# BreakoutPcb.net
KiCad netlist of a schematic drawn in Altium Designer
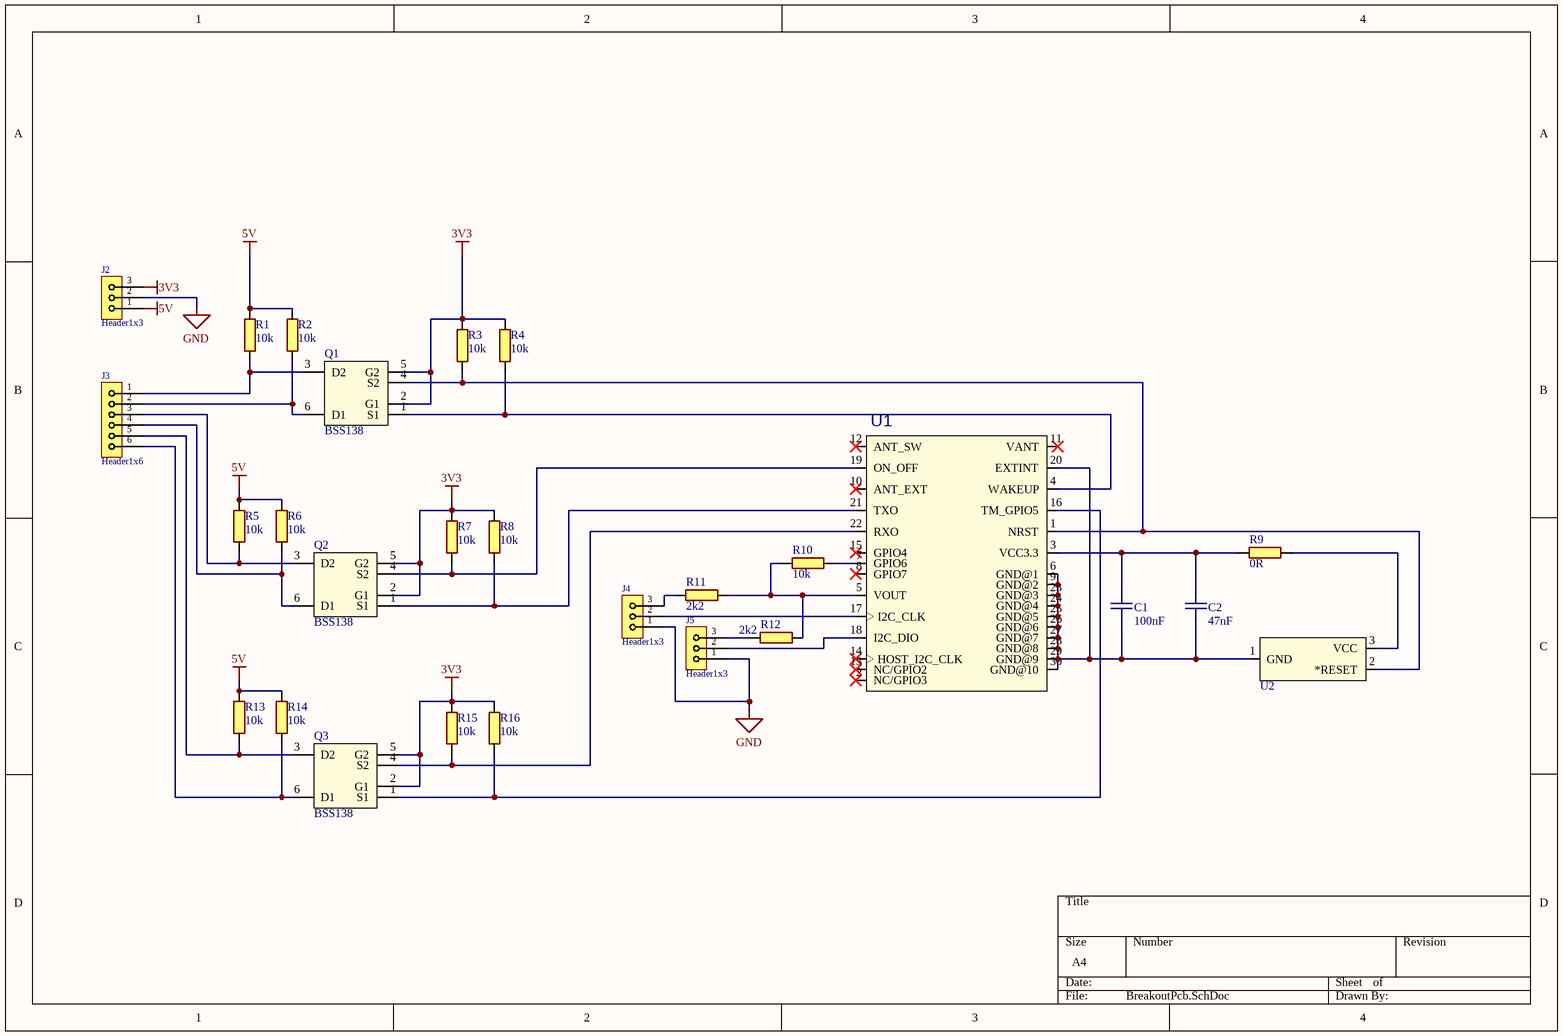
[diagram p0: BreakoutPcb.SchDoc]

(export (version "E")
  (design (tool "Eeschema 10.0.6"))
  (components
    (comp (ref "C1")
      (value "100nF")
      (footprint "CAPC0603(1608)55_N")
      (description "X7R 50V 5%")
      (libsource (lib "OVLib") (part "CAP"))
    )
    (comp (ref "C2")
      (value "47nF")
      (footprint "CAPC0805(2012)100_N")
      (description "X7R")
      (libsource (lib "OVLib") (part "CAP"))
    )
    (comp (ref "J2")
      (value "Header1x3")
      (footprint "HDRV3W64P254_1X3_762X254X900B")
      (libsource (lib "OVLib") (part "Header1x3"))
    )
    (comp (ref "J3")
      (value "Header1x6")
      (footprint "HDRV6W64P254_1X6_1524X254X900B")
      (libsource (lib "OVLib") (part "Header1x6"))
    )
    (comp (ref "J4")
      (value "Header1x3")
      (footprint "HDRV3W64P254_1X3_762X254X900B")
      (libsource (lib "OVLib") (part "Header1x3"))
    )
    (comp (ref "J5")
      (value "Header1x3")
      (footprint "HDRV3W64P254_1X3_762X254X900B")
      (libsource (lib "OVLib") (part "Header1x3"))
    )
    (comp (ref "Q1")
      (value "BSS138")
      (footprint "PCBComponent_1")
      (description "FET SM NCH 50V 220mA SOT23-3L")
      (libsource (lib "BSS138") (part "BSS138"))
    )
    (comp (ref "Q2")
      (value "BSS138")
      (footprint "PCBComponent_1")
      (description "FET SM NCH 50V 220mA SOT23-3L")
      (libsource (lib "BSS138") (part "BSS138"))
    )
    (comp (ref "Q3")
      (value "BSS138")
      (footprint "PCBComponent_1")
      (description "FET SM NCH 50V 220mA SOT23-3L")
      (libsource (lib "BSS138") (part "BSS138"))
    )
    (comp (ref "R1")
      (value "10k")
      (footprint "RESC0603(1608)_N")
      (description "0.1W 1% Thick film resistor")
      (libsource (lib "OVLib") (part "Resistor2"))
    )
    (comp (ref "R2")
      (value "10k")
      (footprint "RESC0603(1608)_N")
      (description "0.1W 1% Thick film resistor")
      (libsource (lib "OVLib") (part "Resistor2"))
    )
    (comp (ref "R3")
      (value "10k")
      (footprint "RESC0603(1608)_N")
      (description "0.1W 1% Thick film resistor")
      (libsource (lib "OVLib") (part "Resistor2"))
    )
    (comp (ref "R4")
      (value "10k")
      (footprint "RESC0603(1608)_N")
      (description "0.1W 1% Thick film resistor")
      (libsource (lib "OVLib") (part "Resistor2"))
    )
    (comp (ref "R5")
      (value "10k")
      (footprint "RESC0603(1608)_N")
      (description "0.1W 1% Thick film resistor")
      (libsource (lib "OVLib") (part "Resistor2"))
    )
    (comp (ref "R6")
      (value "10k")
      (footprint "RESC0603(1608)_N")
      (description "0.1W 1% Thick film resistor")
      (libsource (lib "OVLib") (part "Resistor2"))
    )
    (comp (ref "R7")
      (value "10k")
      (footprint "RESC0603(1608)_N")
      (description "0.1W 1% Thick film resistor")
      (libsource (lib "OVLib") (part "Resistor2"))
    )
    (comp (ref "R8")
      (value "10k")
      (footprint "RESC0603(1608)_N")
      (description "0.1W 1% Thick film resistor")
      (libsource (lib "OVLib") (part "Resistor2"))
    )
    (comp (ref "R9")
      (value "0R")
      (footprint "RESC0603(1608)_N")
      (description "0.1W 1% Thick film resistor")
      (libsource (lib "") (part "Resistor2_1"))
    )
    (comp (ref "R10")
      (value "10k")
      (footprint "RESC0603(1608)_N")
      (description "0.1W 1% Thick film resistor")
      (libsource (lib "") (part "Resistor2_1"))
    )
    (comp (ref "R11")
      (value "2k2")
      (footprint "RESC0603(1608)_N")
      (description "0.1W 1% Thick film resistor")
      (libsource (lib "") (part "Resistor2_1"))
    )
    (comp (ref "R12")
      (value "2k2")
      (footprint "RESC0603(1608)_N")
      (description "0.1W 1% Thick film resistor")
      (libsource (lib "") (part "Resistor2_1"))
    )
    (comp (ref "R13")
      (value "10k")
      (footprint "RESC0603(1608)_N")
      (description "0.1W 1% Thick film resistor")
      (libsource (lib "OVLib") (part "Resistor2"))
    )
    (comp (ref "R14")
      (value "10k")
      (footprint "RESC0603(1608)_N")
      (description "0.1W 1% Thick film resistor")
      (libsource (lib "OVLib") (part "Resistor2"))
    )
    (comp (ref "R15")
      (value "10k")
      (footprint "RESC0603(1608)_N")
      (description "0.1W 1% Thick film resistor")
      (libsource (lib "OVLib") (part "Resistor2"))
    )
    (comp (ref "R16")
      (value "10k")
      (footprint "RESC0603(1608)_N")
      (description "0.1W 1% Thick film resistor")
      (libsource (lib "OVLib") (part "Resistor2"))
    )
    (comp (ref "U1")
      (value "A2235-H")
      (footprint "XCVR_A2235-H")
      (description "Gps Module, Mini Outline w/ Ant")
      (fields (field (name "MF") "Maestro Wireless"))
      (libsource (lib "A2235-H") (part "A2235-H"))
    )
    (comp (ref "U2")
      (value "MAX809SEXR-T")
      (footprint "21-0075D")
      (description "PMIC - system monitor Maxim Integrated MAX809SEXR+T Reset/power-on reset SC 70 3")
      (fields (field (name "MP") "MAX809SEXR+T") (field (name "MF") "Maxim Integrated"))
      (libsource (lib "MAX809SEXR-T") (part "MAX809SEXR-T"))
    )
  )
  (nets
    (net (code "1") (name "3V3") (class "Default")
      (node (ref "J2") (pin "3") (pinfunction "3_3") (pintype "passive"))
      (node (ref "Q1") (pin "2") (pinfunction "G1_2") (pintype "passive"))
      (node (ref "Q1") (pin "5") (pinfunction "G2_5") (pintype "passive"))
      (node (ref "Q2") (pin "2") (pinfunction "G1_2") (pintype "passive"))
      (node (ref "Q2") (pin "5") (pinfunction "G2_5") (pintype "passive"))
      (node (ref "Q3") (pin "2") (pinfunction "G1_2") (pintype "passive"))
      (node (ref "Q3") (pin "5") (pinfunction "G2_5") (pintype "passive"))
      (node (ref "R15") (pin "2") (pinfunction "2_2") (pintype "passive"))
      (node (ref "R16") (pin "2") (pinfunction "2_2") (pintype "passive"))
      (node (ref "R3") (pin "2") (pinfunction "2_2") (pintype "passive"))
      (node (ref "R4") (pin "2") (pinfunction "2_2") (pintype "passive"))
      (node (ref "R7") (pin "2") (pinfunction "2_2") (pintype "passive"))
      (node (ref "R8") (pin "2") (pinfunction "2_2") (pintype "passive"))
    )
    (net (code "2") (name "5V") (class "Default")
      (node (ref "J2") (pin "1") (pinfunction "1_1") (pintype "passive"))
      (node (ref "R1") (pin "2") (pinfunction "2_2") (pintype "passive"))
      (node (ref "R13") (pin "2") (pinfunction "2_2") (pintype "passive"))
      (node (ref "R14") (pin "2") (pinfunction "2_2") (pintype "passive"))
      (node (ref "R2") (pin "2") (pinfunction "2_2") (pintype "passive"))
      (node (ref "R5") (pin "2") (pinfunction "2_2") (pintype "passive"))
      (node (ref "R6") (pin "2") (pinfunction "2_2") (pintype "passive"))
    )
    (net (code "3") (name "GND") (class "Default")
      (node (ref "J2") (pin "2") (pinfunction "2_2") (pintype "passive"))
      (node (ref "J4") (pin "1") (pinfunction "1_1") (pintype "passive"))
      (node (ref "J5") (pin "1") (pinfunction "1_1") (pintype "passive"))
    )
    (net (code "4") (name "Net-(J4-Pad3)") (class "Default")
      (node (ref "J4") (pin "3") (pinfunction "3_3") (pintype "passive"))
      (node (ref "R11") (pin "1") (pinfunction "1_1") (pintype "passive"))
    )
    (net (code "5") (name "Net-(J5-Pad3)") (class "Default")
      (node (ref "J5") (pin "3") (pinfunction "3_3") (pintype "passive"))
      (node (ref "R12") (pin "1") (pinfunction "1_1") (pintype "passive"))
    )
    (net (code "6") (name "Net-(Q1-D1)") (class "Default")
      (node (ref "J3") (pin "2") (pinfunction "2_2") (pintype "passive"))
      (node (ref "Q1") (pin "6") (pinfunction "D1_6") (pintype "passive"))
      (node (ref "R2") (pin "1") (pinfunction "1_1") (pintype "passive"))
    )
    (net (code "7") (name "Net-(Q1-D2)") (class "Default")
      (node (ref "J3") (pin "1") (pinfunction "1_1") (pintype "passive"))
      (node (ref "Q1") (pin "3") (pinfunction "D2_3") (pintype "passive"))
      (node (ref "R1") (pin "1") (pinfunction "1_1") (pintype "passive"))
    )
    (net (code "8") (name "Net-(Q1-S1)") (class "Default")
      (node (ref "Q1") (pin "1") (pinfunction "S1_1") (pintype "passive"))
      (node (ref "R4") (pin "1") (pinfunction "1_1") (pintype "passive"))
      (node (ref "U1") (pin "4") (pinfunction "WAKEUP_4") (pintype "output"))
    )
    (net (code "9") (name "Net-(Q1-S2)") (class "Default")
      (node (ref "Q1") (pin "4") (pinfunction "S2_4") (pintype "passive"))
      (node (ref "R3") (pin "1") (pinfunction "1_1") (pintype "passive"))
      (node (ref "U1") (pin "1") (pinfunction "NRST_1") (pintype "input"))
      (node (ref "U2") (pin "2") (pinfunction "*RESET_2") (pintype "output"))
    )
    (net (code "10") (name "Net-(Q2-D1)") (class "Default")
      (node (ref "J3") (pin "4") (pinfunction "4_4") (pintype "passive"))
      (node (ref "Q2") (pin "6") (pinfunction "D1_6") (pintype "passive"))
      (node (ref "R6") (pin "1") (pinfunction "1_1") (pintype "passive"))
    )
    (net (code "11") (name "Net-(Q2-D2)") (class "Default")
      (node (ref "J3") (pin "3") (pinfunction "3_3") (pintype "passive"))
      (node (ref "Q2") (pin "3") (pinfunction "D2_3") (pintype "passive"))
      (node (ref "R5") (pin "1") (pinfunction "1_1") (pintype "passive"))
    )
    (net (code "12") (name "Net-(Q2-S1)") (class "Default")
      (node (ref "Q2") (pin "1") (pinfunction "S1_1") (pintype "passive"))
      (node (ref "R8") (pin "1") (pinfunction "1_1") (pintype "passive"))
      (node (ref "U1") (pin "21") (pinfunction "TXO_21") (pintype "output"))
    )
    (net (code "13") (name "Net-(Q2-S2)") (class "Default")
      (node (ref "Q2") (pin "4") (pinfunction "S2_4") (pintype "passive"))
      (node (ref "R7") (pin "1") (pinfunction "1_1") (pintype "passive"))
      (node (ref "U1") (pin "19") (pinfunction "ON_OFF_19") (pintype "input"))
    )
    (net (code "14") (name "Net-(Q3-D1)") (class "Default")
      (node (ref "J3") (pin "6") (pinfunction "6_6") (pintype "passive"))
      (node (ref "Q3") (pin "6") (pinfunction "D1_6") (pintype "passive"))
      (node (ref "R14") (pin "1") (pinfunction "1_1") (pintype "passive"))
    )
    (net (code "15") (name "Net-(Q3-D2)") (class "Default")
      (node (ref "J3") (pin "5") (pinfunction "5_5") (pintype "passive"))
      (node (ref "Q3") (pin "3") (pinfunction "D2_3") (pintype "passive"))
      (node (ref "R13") (pin "1") (pinfunction "1_1") (pintype "passive"))
    )
    (net (code "16") (name "Net-(Q3-S1)") (class "Default")
      (node (ref "Q3") (pin "1") (pinfunction "S1_1") (pintype "passive"))
      (node (ref "R16") (pin "1") (pinfunction "1_1") (pintype "passive"))
      (node (ref "U1") (pin "16") (pinfunction "TM_GPIO5_16") (pintype "output"))
    )
    (net (code "17") (name "Net-(Q3-S2)") (class "Default")
      (node (ref "Q3") (pin "4") (pinfunction "S2_4") (pintype "passive"))
      (node (ref "R15") (pin "1") (pinfunction "1_1") (pintype "passive"))
      (node (ref "U1") (pin "22") (pinfunction "RXO_22") (pintype "input"))
    )
    (net (code "18") (name "Net-(U1-EXTINT)") (class "Default")
      (node (ref "C1") (pin "1") (pinfunction "1_1") (pintype "passive"))
      (node (ref "C2") (pin "1") (pinfunction "1_1") (pintype "passive"))
      (node (ref "U1") (pin "20") (pinfunction "EXTINT_20") (pintype "input"))
      (node (ref "U1") (pin "23") (pinfunction "GND@3_23") (pintype "power_in"))
      (node (ref "U1") (pin "24") (pinfunction "GND@4_24") (pintype "power_in"))
      (node (ref "U1") (pin "25") (pinfunction "GND@5_25") (pintype "power_in"))
      (node (ref "U1") (pin "26") (pinfunction "GND@6_26") (pintype "power_in"))
      (node (ref "U1") (pin "27") (pinfunction "GND@7_27") (pintype "power_in"))
      (node (ref "U1") (pin "28") (pinfunction "GND@8_28") (pintype "power_in"))
      (node (ref "U1") (pin "29") (pinfunction "GND@9_29") (pintype "power_in"))
      (node (ref "U1") (pin "30") (pinfunction "GND@10_30") (pintype "power_in"))
      (node (ref "U1") (pin "6") (pinfunction "GND@1_6") (pintype "power_in"))
      (node (ref "U1") (pin "9") (pinfunction "GND@2_9") (pintype "power_in"))
      (node (ref "U2") (pin "1") (pinfunction "GND_1") (pintype "power_in"))
    )
    (net (code "19") (name "Net-(U1-GPIO6)") (class "Default")
      (node (ref "R10") (pin "2") (pinfunction "2_2") (pintype "passive"))
      (node (ref "U1") (pin "7") (pinfunction "GPIO6_7") (pintype "input"))
    )
    (net (code "20") (name "Net-(U1-I2C_CLK)") (class "Default")
      (node (ref "J4") (pin "2") (pinfunction "2_2") (pintype "passive"))
      (node (ref "U1") (pin "17") (pinfunction "I2C_CLK_17") (pintype "bidirectional"))
    )
    (net (code "21") (name "Net-(U1-I2C_DIO)") (class "Default")
      (node (ref "J5") (pin "2") (pinfunction "2_2") (pintype "passive"))
      (node (ref "U1") (pin "18") (pinfunction "I2C_DIO_18") (pintype "bidirectional"))
    )
    (net (code "22") (name "Net-(U1-VCC3.3)") (class "Default")
      (node (ref "C1") (pin "2") (pinfunction "2_2") (pintype "passive"))
      (node (ref "C2") (pin "2") (pinfunction "2_2") (pintype "passive"))
      (node (ref "R9") (pin "1") (pinfunction "1_1") (pintype "passive"))
      (node (ref "U1") (pin "3") (pinfunction "VCC3.3_3") (pintype "power_in"))
    )
    (net (code "23") (name "Net-(U1-VOUT)") (class "Default")
      (node (ref "R10") (pin "1") (pinfunction "1_1") (pintype "passive"))
      (node (ref "R11") (pin "2") (pinfunction "2_2") (pintype "passive"))
      (node (ref "R12") (pin "2") (pinfunction "2_2") (pintype "passive"))
      (node (ref "U1") (pin "5") (pinfunction "VOUT_5") (pintype "output"))
    )
    (net (code "24") (name "Net-(U2-VCC)") (class "Default")
      (node (ref "R9") (pin "2") (pinfunction "2_2") (pintype "passive"))
      (node (ref "U2") (pin "3") (pinfunction "VCC_3") (pintype "power_in"))
    )
    (net (code "25") (name "unconnected-(U1-ANT_EXT-Pad10)") (class "Default")
      (node (ref "U1") (pin "10") (pinfunction "ANT_EXT_10") (pintype "input+no_connect"))
    )
    (net (code "26") (name "unconnected-(U1-ANT_SW-Pad12)") (class "Default")
      (node (ref "U1") (pin "12") (pinfunction "ANT_SW_12") (pintype "input+no_connect"))
    )
    (net (code "27") (name "unconnected-(U1-GPIO4-Pad15)") (class "Default")
      (node (ref "U1") (pin "15") (pinfunction "GPIO4_15") (pintype "input+no_connect"))
    )
    (net (code "28") (name "unconnected-(U1-GPIO7-Pad8)") (class "Default")
      (node (ref "U1") (pin "8") (pinfunction "GPIO7_8") (pintype "input+no_connect"))
    )
    (net (code "29") (name "unconnected-(U1-HOST_I2C_CLK-Pad14)") (class "Default")
      (node (ref "U1") (pin "14") (pinfunction "HOST_I2C_CLK_14") (pintype "bidirectional+no_connect"))
    )
    (net (code "30") (name "unconnected-(U1-NC{slash}GPIO2-Pad13)") (class "Default")
      (node (ref "U1") (pin "13") (pinfunction "NC/GPIO2_13") (pintype "bidirectional+no_connect"))
    )
    (net (code "31") (name "unconnected-(U1-NC{slash}GPIO3-Pad2)") (class "Default")
      (node (ref "U1") (pin "2") (pinfunction "NC/GPIO3_2") (pintype "bidirectional+no_connect"))
    )
    (net (code "32") (name "unconnected-(U1-VANT-Pad11)") (class "Default")
      (node (ref "U1") (pin "11") (pinfunction "VANT_11") (pintype "power_in+no_connect"))
    )
  )
)
